# SW6124_A_A_B_C_Lighting_MCU_SEG.net
KiCad netlist of a schematic drawn in Altium Designer
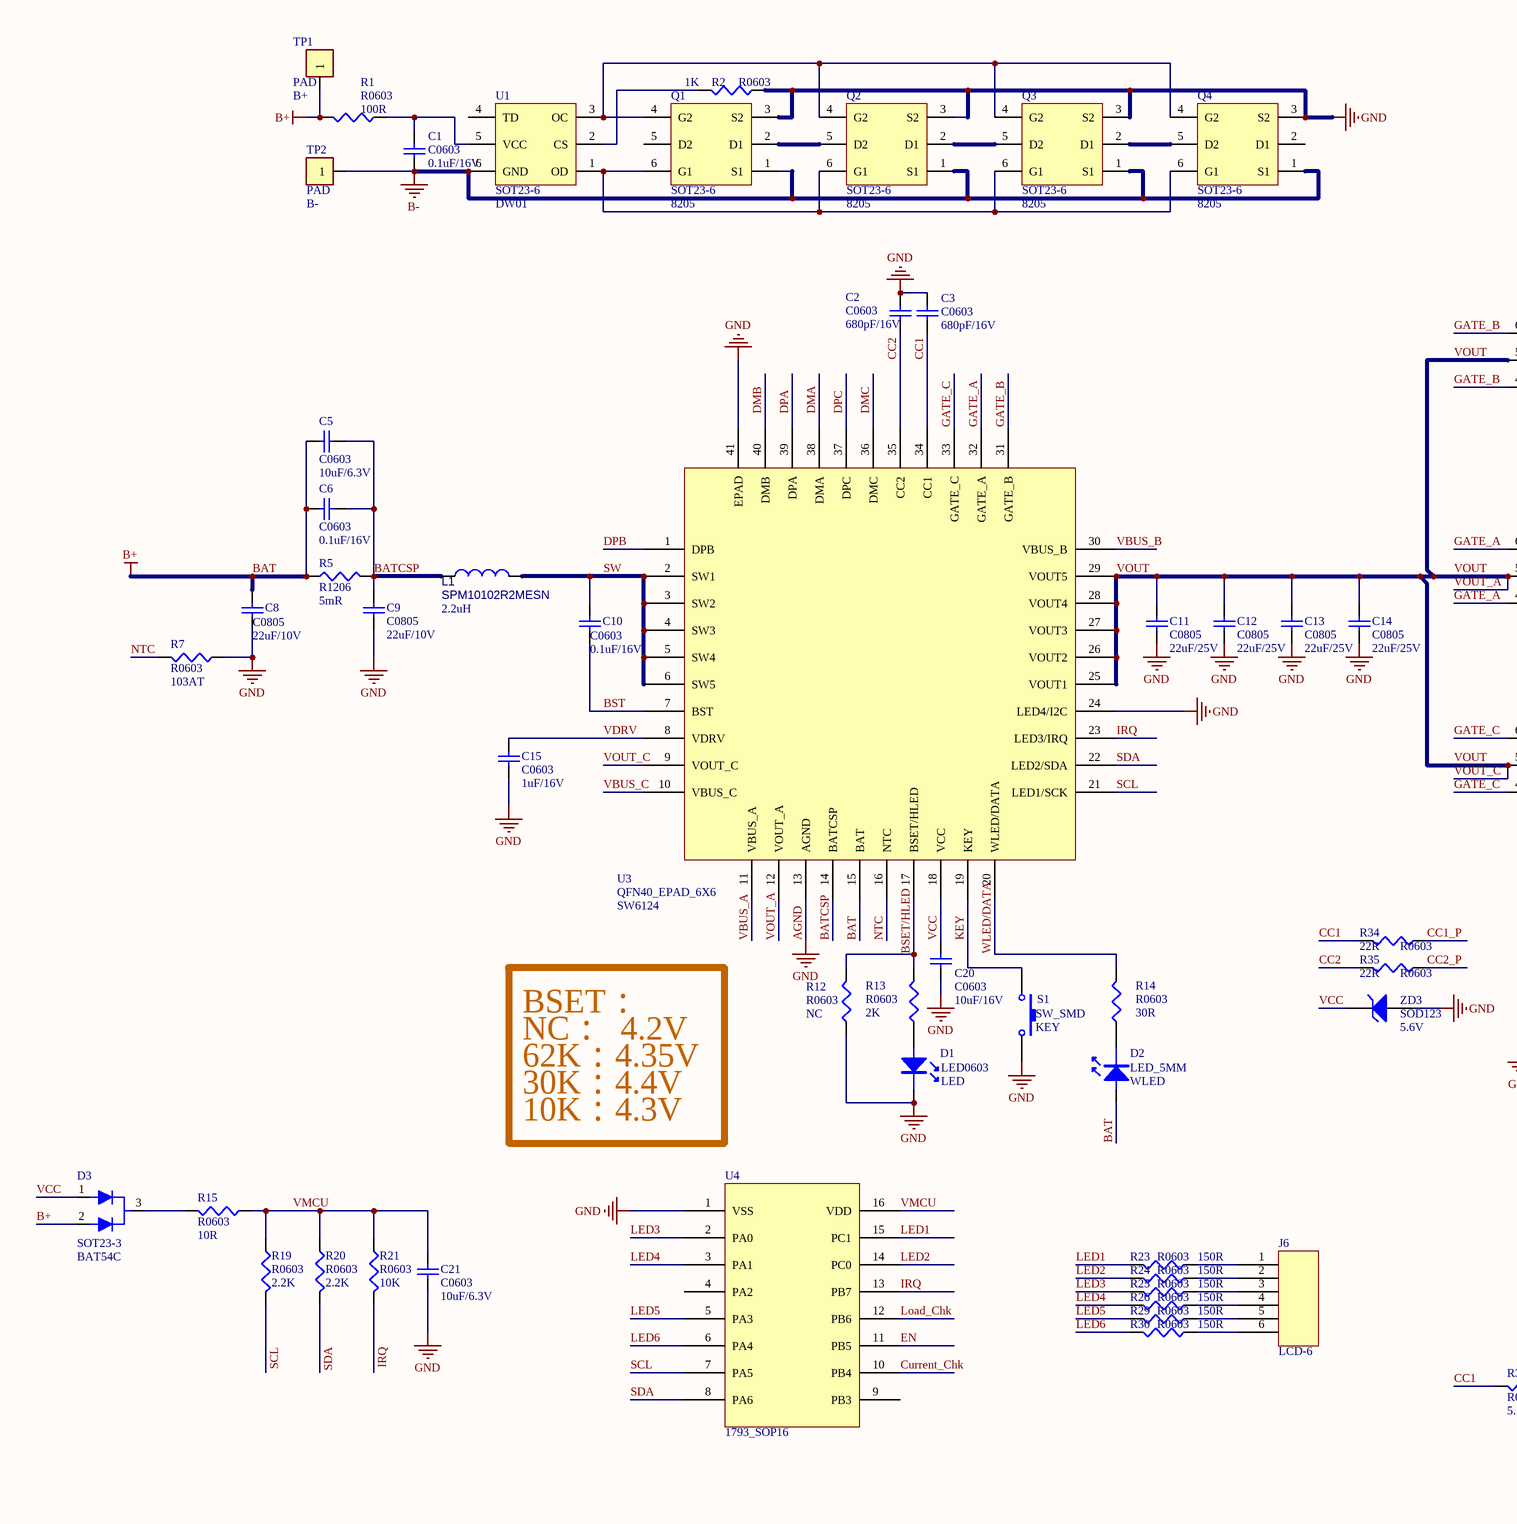
[diagram p0: SW6124+A+A+B+C+Lighting+MCU+SEG.SchDoc, left]
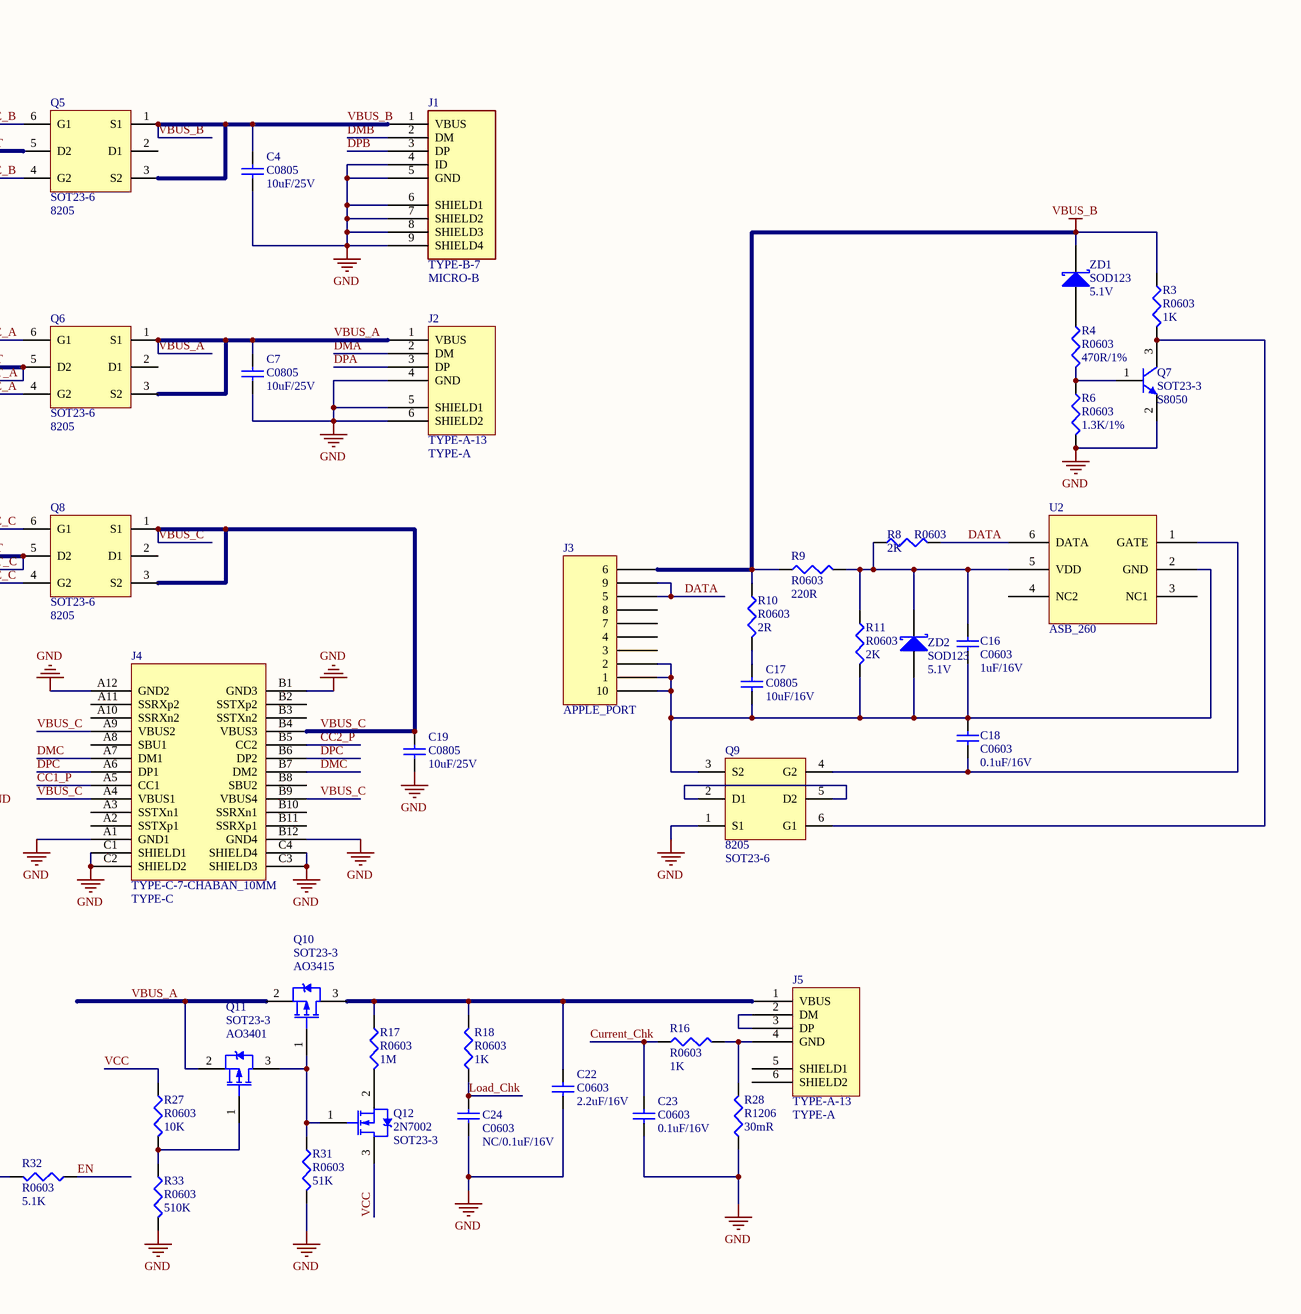
[diagram p1: SW6124+A+A+B+C+Lighting+MCU+SEG.SchDoc, right]

(export (version "E")
  (design (tool "Eeschema 10.0.6"))
  (components
    (comp (ref "C1")
      (value "C0603")
      (footprint "C0603")
      (description "Capacitor")
      (fields (field (name "ALTIUM_VALUE") "0.1uF/16V") (field (name "PUBLISHER") "Altium Limited"))
      (libsource (lib "*") (part "Cap"))
    )
    (comp (ref "C2")
      (value "C0603")
      (footprint "C0603")
      (description "Capacitor")
      (fields (field (name "ALTIUM_VALUE") "680pF/16V") (field (name "PUBLISHER") "Altium Limited"))
      (libsource (lib "*") (part "CAP0603"))
    )
    (comp (ref "C3")
      (value "C0603")
      (footprint "C0603")
      (description "Capacitor")
      (fields (field (name "ALTIUM_VALUE") "680pF/16V") (field (name "PUBLISHER") "Altium Limited"))
      (libsource (lib "*") (part "CAP0603"))
    )
    (comp (ref "C4")
      (value "C0805")
      (footprint "C0805")
      (description "Capacitor")
      (fields (field (name "ALTIUM_VALUE") "10uF/25V") (field (name "PUBLISHER") "Altium Limited"))
      (libsource (lib "*") (part "CAP0603"))
    )
    (comp (ref "C5")
      (value "C0603")
      (footprint "C0603")
      (description "Capacitor")
      (fields (field (name "ALTIUM_VALUE") "10uF/6.3V") (field (name "PUBLISHER") "Altium Limited"))
      (libsource (lib "*") (part "CAP0603"))
    )
    (comp (ref "C6")
      (value "C0603")
      (footprint "C0603")
      (description "Capacitor")
      (fields (field (name "ALTIUM_VALUE") "0.1uF/16V") (field (name "PUBLISHER") "Altium Limited"))
      (libsource (lib "*") (part "CAP0603"))
    )
    (comp (ref "C7")
      (value "C0805")
      (footprint "C0805")
      (description "Capacitor")
      (fields (field (name "ALTIUM_VALUE") "10uF/25V") (field (name "PUBLISHER") "Altium Limited"))
      (libsource (lib "*") (part "CAP0603"))
    )
    (comp (ref "C8")
      (value "C0805")
      (footprint "C0805")
      (description "Capacitor")
      (fields (field (name "ALTIUM_VALUE") "22uF/10V") (field (name "PUBLISHER") "Altium Limited"))
      (libsource (lib "*") (part "CAP0805"))
    )
    (comp (ref "C9")
      (value "C0805")
      (footprint "C0805")
      (description "Capacitor")
      (fields (field (name "ALTIUM_VALUE") "22uF/10V") (field (name "PUBLISHER") "Altium Limited"))
      (libsource (lib "*") (part "CAP0805"))
    )
    (comp (ref "C10")
      (value "C0603")
      (footprint "C0603")
      (description "Capacitor")
      (fields (field (name "ALTIUM_VALUE") "0.1uF/16V") (field (name "PUBLISHER") "Altium Limited"))
      (libsource (lib "*") (part "CAP0603"))
    )
    (comp (ref "C11")
      (value "C0805")
      (footprint "C0805")
      (description "Capacitor")
      (fields (field (name "ALTIUM_VALUE") "22uF/25V") (field (name "PUBLISHER") "Altium Limited"))
      (libsource (lib "*") (part "CAP0805"))
    )
    (comp (ref "C12")
      (value "C0805")
      (footprint "C0805")
      (description "Capacitor")
      (fields (field (name "ALTIUM_VALUE") "22uF/25V") (field (name "PUBLISHER") "Altium Limited"))
      (libsource (lib "*") (part "CAP0805"))
    )
    (comp (ref "C13")
      (value "C0805")
      (footprint "C0805")
      (description "Capacitor")
      (fields (field (name "ALTIUM_VALUE") "22uF/25V") (field (name "PUBLISHER") "Altium Limited"))
      (libsource (lib "*") (part "CAP0805"))
    )
    (comp (ref "C14")
      (value "C0805")
      (footprint "C0805")
      (description "Capacitor")
      (fields (field (name "ALTIUM_VALUE") "22uF/25V") (field (name "PUBLISHER") "Altium Limited"))
      (libsource (lib "*") (part "CAP0805"))
    )
    (comp (ref "C15")
      (value "C0603")
      (footprint "C0603")
      (description "Capacitor")
      (fields (field (name "ALTIUM_VALUE") "1uF/16V") (field (name "PUBLISHER") "Altium Limited"))
      (libsource (lib "*") (part "CAP0603"))
    )
    (comp (ref "C16")
      (value "C0603")
      (footprint "C0603")
      (description "Capacitor")
      (fields (field (name "ALTIUM_VALUE") "1uF/16V") (field (name "PUBLISHER") "Altium Limited"))
      (libsource (lib "*") (part "CAP0805"))
    )
    (comp (ref "C17")
      (value "C0805")
      (footprint "C0805")
      (description "Capacitor")
      (fields (field (name "ALTIUM_VALUE") "10uF/16V") (field (name "PUBLISHER") "Altium Limited"))
      (libsource (lib "*") (part "CAP0805"))
    )
    (comp (ref "C18")
      (value "C0603")
      (footprint "C0603")
      (description "Capacitor")
      (fields (field (name "ALTIUM_VALUE") "0.1uF/16V") (field (name "PUBLISHER") "Altium Limited"))
      (libsource (lib "*") (part "CAP0805"))
    )
    (comp (ref "C19")
      (value "C0805")
      (footprint "C0805")
      (description "Capacitor")
      (fields (field (name "ALTIUM_VALUE") "10uF/25V") (field (name "PUBLISHER") "Altium Limited"))
      (libsource (lib "*") (part "CAP0603"))
    )
    (comp (ref "C20")
      (value "C0603")
      (footprint "C0603")
      (description "Capacitor")
      (fields (field (name "ALTIUM_VALUE") "10uF/16V") (field (name "PUBLISHER") "Altium Limited"))
      (libsource (lib "*") (part "CAP0603"))
    )
    (comp (ref "C21")
      (value "C0603")
      (footprint "C0603")
      (description "Capacitor")
      (fields (field (name "ALTIUM_VALUE") "10uF/6.3V") (field (name "PUBLISHER") "Altium Limited"))
      (libsource (lib "*") (part "CAP0603"))
    )
    (comp (ref "C22")
      (value "C0603")
      (footprint "C0603")
      (description "Capacitor")
      (fields (field (name "ALTIUM_VALUE") "2.2uF/16V") (field (name "PUBLISHER") "Altium Limited"))
      (libsource (lib "*") (part "CAP0603"))
    )
    (comp (ref "C23")
      (value "C0603")
      (footprint "C0603")
      (description "Capacitor")
      (fields (field (name "ALTIUM_VALUE") "0.1uF/16V") (field (name "PUBLISHER") "Altium Limited"))
      (libsource (lib "*") (part "CAP0603"))
    )
    (comp (ref "C24")
      (value "C0603")
      (footprint "C0603")
      (description "Capacitor")
      (fields (field (name "ALTIUM_VALUE") "NC/0.1uF/16V") (field (name "PUBLISHER") "Altium Limited"))
      (libsource (lib "*") (part "CAP0603"))
    )
    (comp (ref "D1") (value "LED") (footprint "LED0603") (libsource (lib "*") (part "LED")))
    (comp (ref "D2")
      (value "WLED")
      (footprint "LED_5MM")
      (fields (field (name "FOOTPRINF") "LED_5MM") (field (name "Comment") "LED_5MM"))
      (libsource (lib "*") (part "LED"))
    )
    (comp (ref "D3") (value "BAT54C") (footprint "SOT23-3") (libsource (lib "Schlib1-2012") (part "D3")))
    (comp (ref "J1")
      (value "MICRO-B")
      (footprint "TYPE-B-7")
      (fields (field (name "FOOTPRINTF") "TYPE-B-7") (field (name "Comment") "USB_MICRO_B"))
      (libsource (lib "*") (part "USB_MICRO_B"))
    )
    (comp (ref "J2")
      (value "TYPE-A")
      (footprint "TYPE-A-13")
      (fields (field (name "FOOTPRINF") "TYPE-A-13") (field (name "Comment") "TYPE-A-1"))
      (libsource (lib "*") (part "TYPE-A-1"))
    )
    (comp (ref "J3") (value "APPLE_PORT") (libsource (lib "TEST") (part "APPLE_PORT")))
    (comp (ref "J4")
      (value "TYPE-C")
      (footprint "TYPE-C-7-CHABAN_10MM")
      (libsource (lib "*") (part "TYPE-C"))
    )
    (comp (ref "J5")
      (value "TYPE-A")
      (footprint "PIE10-USB")
      (fields (field (name "FOOTPRINF") "TYPE-A-13") (field (name "Comment") "TYPE-A-1"))
      (libsource (lib "*") (part "TYPE-A-1"))
    )
    (comp (ref "J6") (value "LCD-6") (libsource (lib "TEST") (part "LCD-6")))
    (comp (ref "L1")
      (value "SPM10102R2MESN")
      (footprint "INDUCTOR_SPM1010")
      (fields (field (name "ALTIUM_VALUE") "2.2uH"))
      (libsource (lib "*") (part "INDUCTOR"))
    )
    (comp (ref "Q1")
      (value "8205")
      (footprint "SOT23-6")
      (fields (field (name "FOOTPRINF") "SOT23-6"))
      (libsource (lib "") (part "8205B_2"))
    )
    (comp (ref "Q2")
      (value "8205")
      (footprint "SOT23-6")
      (fields (field (name "FOOTPRINF") "SOT23-6"))
      (libsource (lib "") (part "8205B_2"))
    )
    (comp (ref "Q3")
      (value "8205")
      (footprint "SOT23-6")
      (fields (field (name "FOOTPRINF") "SOT23-6"))
      (libsource (lib "") (part "8205B_2"))
    )
    (comp (ref "Q4")
      (value "8205")
      (footprint "SOT23-6")
      (fields (field (name "FOOTPRINF") "SOT23-6"))
      (libsource (lib "") (part "8205B_2"))
    )
    (comp (ref "Q5")
      (value "8205")
      (footprint "SOT23-6")
      (fields (field (name "FOOTPRINF") "SOT23-6"))
      (libsource (lib "") (part "8205B_1"))
    )
    (comp (ref "Q6")
      (value "8205")
      (footprint "SOT23-6")
      (fields (field (name "FOOTPRINF") "SOT23-6"))
      (libsource (lib "") (part "8205B_1"))
    )
    (comp (ref "Q7")
      (value "S8050")
      (footprint "SOT23-3")
      (description "NPN General Purpose Amplifier")
      (fields (field (name "PUBLISHER") "Altium Limited"))
      (libsource (lib "Miscellaneous Devices") (part "2N3904"))
    )
    (comp (ref "Q8")
      (value "8205")
      (footprint "SOT23-6")
      (fields (field (name "FOOTPRINF") "SOT23-6"))
      (libsource (lib "") (part "8205B_1"))
    )
    (comp (ref "Q9")
      (value "8205")
      (footprint "SOT23-6")
      (fields (field (name "FOOTPRINF") "SOT23-6"))
      (libsource (lib "*") (part "8205B"))
    )
    (comp (ref "Q10")
      (value "AO3415")
      (footprint "SOT23-3")
      (description "P-Channel Power MOSFET")
      (fields (field (name "Comment") "PMOS-2") (field (name "PUBLISHER") "Altium Limited"))
      (libsource (lib "Miscellaneous Devices") (part "PMOS-2"))
    )
    (comp (ref "Q11")
      (value "AO3401")
      (footprint "SOT23-3")
      (description "P-Channel Power MOSFET")
      (fields (field (name "Comment") "PMOS-2") (field (name "PUBLISHER") "Altium Limited"))
      (libsource (lib "Miscellaneous Devices") (part "PMOS-2"))
    )
    (comp (ref "Q12")
      (value "2N7002")
      (footprint "SOT23-3")
      (description "N-Channel Power MOSFET")
      (fields (field (name "Comment") "NMOS-2") (field (name "PUBLISHER") "Altium Limited"))
      (libsource (lib "Miscellaneous Devices") (part "NMOS-2"))
    )
    (comp (ref "R1")
      (value "R0603")
      (footprint "R0603")
      (description "Resistor")
      (fields (field (name "ALTIUM_VALUE") "100R") (field (name "PUBLISHER") "Altium Limited"))
      (libsource (lib "*") (part "Res3"))
    )
    (comp (ref "R2")
      (value "R0603")
      (footprint "R0603")
      (description "Resistor")
      (fields (field (name "ALTIUM_VALUE") "1K") (field (name "PUBLISHER") "Altium Limited"))
      (libsource (lib "*") (part "Res3"))
    )
    (comp (ref "R3")
      (value "R0603")
      (footprint "R0603")
      (description "Resistor")
      (fields (field (name "ALTIUM_VALUE") "1K") (field (name "PUBLISHER") "Altium Limited"))
      (libsource (lib "Miscellaneous Devices") (part "Res3"))
    )
    (comp (ref "R4")
      (value "R0603")
      (footprint "R0603")
      (description "Resistor")
      (fields (field (name "ALTIUM_VALUE") "470R/1%") (field (name "PUBLISHER") "Altium Limited"))
      (libsource (lib "Miscellaneous Devices") (part "Res3"))
    )
    (comp (ref "R5")
      (value "R1206")
      (footprint "R1206")
      (description "Resistor")
      (fields (field (name "ALTIUM_VALUE") "5mR") (field (name "PUBLISHER") "Altium Limited"))
      (libsource (lib "*") (part "RES"))
    )
    (comp (ref "R6")
      (value "R0603")
      (footprint "R0603")
      (description "Resistor")
      (fields (field (name "ALTIUM_VALUE") "1.3K/1%") (field (name "PUBLISHER") "Altium Limited"))
      (libsource (lib "Miscellaneous Devices") (part "Res3"))
    )
    (comp (ref "R7")
      (value "R0603")
      (footprint "R0603")
      (description "Resistor")
      (fields (field (name "ALTIUM_VALUE") "103AT") (field (name "PUBLISHER") "Altium Limited"))
      (libsource (lib "*") (part "RES"))
    )
    (comp (ref "R8")
      (value "R0603")
      (footprint "R0603")
      (description "Resistor")
      (fields (field (name "ALTIUM_VALUE") "2K") (field (name "PUBLISHER") "Altium Limited"))
      (libsource (lib "Miscellaneous Devices") (part "Res3"))
    )
    (comp (ref "R9")
      (value "R0603")
      (footprint "R0603")
      (description "Resistor")
      (fields (field (name "ALTIUM_VALUE") "220R") (field (name "PUBLISHER") "Altium Limited"))
      (libsource (lib "Miscellaneous Devices") (part "Res3"))
    )
    (comp (ref "R10")
      (value "R0603")
      (footprint "R0603")
      (description "Resistor")
      (fields (field (name "ALTIUM_VALUE") "2R") (field (name "PUBLISHER") "Altium Limited"))
      (libsource (lib "Miscellaneous Devices") (part "Res3"))
    )
    (comp (ref "R11")
      (value "R0603")
      (footprint "R0603")
      (description "Resistor")
      (fields (field (name "ALTIUM_VALUE") "2K") (field (name "PUBLISHER") "Altium Limited"))
      (libsource (lib "Miscellaneous Devices") (part "Res3"))
    )
    (comp (ref "R12")
      (value "R0603")
      (footprint "R0603")
      (description "Resistor")
      (fields (field (name "ALTIUM_VALUE") "NC") (field (name "PUBLISHER") "Altium Limited"))
      (libsource (lib "*") (part "RES"))
    )
    (comp (ref "R13")
      (value "R0603")
      (footprint "R0603")
      (description "Resistor")
      (fields (field (name "ALTIUM_VALUE") "2K") (field (name "PUBLISHER") "Altium Limited"))
      (libsource (lib "*") (part "RES"))
    )
    (comp (ref "R14")
      (value "R0603")
      (footprint "R0603")
      (description "Resistor")
      (fields (field (name "ALTIUM_VALUE") "30R") (field (name "PUBLISHER") "Altium Limited"))
      (libsource (lib "*") (part "RES"))
    )
    (comp (ref "R15")
      (value "R0603")
      (footprint "R0603")
      (description "Resistor")
      (fields (field (name "ALTIUM_VALUE") "10R") (field (name "PUBLISHER") "Altium Limited"))
      (libsource (lib "*") (part "RES"))
    )
    (comp (ref "R16")
      (value "R0603")
      (footprint "R0603")
      (description "Resistor")
      (fields (field (name "ALTIUM_VALUE") "1K") (field (name "PUBLISHER") "Altium Limited"))
      (libsource (lib "*") (part "RES"))
    )
    (comp (ref "R17")
      (value "R0603")
      (footprint "R0603")
      (description "Resistor")
      (fields (field (name "ALTIUM_VALUE") "1M") (field (name "PUBLISHER") "Altium Limited"))
      (libsource (lib "*") (part "RES"))
    )
    (comp (ref "R18")
      (value "R0603")
      (footprint "R0603")
      (description "Resistor")
      (fields (field (name "ALTIUM_VALUE") "1K") (field (name "PUBLISHER") "Altium Limited"))
      (libsource (lib "*") (part "RES"))
    )
    (comp (ref "R19")
      (value "R0603")
      (footprint "R0603")
      (description "Resistor")
      (fields (field (name "ALTIUM_VALUE") "2.2K") (field (name "PUBLISHER") "Altium Limited"))
      (libsource (lib "*") (part "RES"))
    )
    (comp (ref "R20")
      (value "R0603")
      (footprint "R0603")
      (description "Resistor")
      (fields (field (name "ALTIUM_VALUE") "2.2K") (field (name "PUBLISHER") "Altium Limited"))
      (libsource (lib "*") (part "RES"))
    )
    (comp (ref "R21")
      (value "R0603")
      (footprint "R0603")
      (description "Resistor")
      (fields (field (name "ALTIUM_VALUE") "10K") (field (name "PUBLISHER") "Altium Limited"))
      (libsource (lib "*") (part "RES"))
    )
    (comp (ref "R23")
      (value "R0603")
      (footprint "R0603")
      (description "Resistor")
      (fields (field (name "ALTIUM_VALUE") "150R") (field (name "PUBLISHER") "Altium Limited"))
      (libsource (lib "*") (part "RES"))
    )
    (comp (ref "R24")
      (value "R0603")
      (footprint "R0603")
      (description "Resistor")
      (fields (field (name "ALTIUM_VALUE") "150R") (field (name "PUBLISHER") "Altium Limited"))
      (libsource (lib "*") (part "RES"))
    )
    (comp (ref "R25")
      (value "R0603")
      (footprint "R0603")
      (description "Resistor")
      (fields (field (name "ALTIUM_VALUE") "150R") (field (name "PUBLISHER") "Altium Limited"))
      (libsource (lib "*") (part "RES"))
    )
    (comp (ref "R26")
      (value "R0603")
      (footprint "R0603")
      (description "Resistor")
      (fields (field (name "ALTIUM_VALUE") "150R") (field (name "PUBLISHER") "Altium Limited"))
      (libsource (lib "*") (part "RES"))
    )
    (comp (ref "R27")
      (value "R0603")
      (footprint "R0603")
      (description "Resistor")
      (fields (field (name "ALTIUM_VALUE") "10K") (field (name "PUBLISHER") "Altium Limited"))
      (libsource (lib "*") (part "RES"))
    )
    (comp (ref "R28")
      (value "R1206")
      (footprint "C-1206A")
      (description "Resistor")
      (fields (field (name "ALTIUM_VALUE") "30mR") (field (name "PUBLISHER") "Altium Limited"))
      (libsource (lib "*") (part "RES"))
    )
    (comp (ref "R29")
      (value "R0603")
      (footprint "R0603")
      (description "Resistor")
      (fields (field (name "ALTIUM_VALUE") "150R") (field (name "PUBLISHER") "Altium Limited"))
      (libsource (lib "*") (part "RES"))
    )
    (comp (ref "R30")
      (value "R0603")
      (footprint "R0603")
      (description "Resistor")
      (fields (field (name "ALTIUM_VALUE") "150R") (field (name "PUBLISHER") "Altium Limited"))
      (libsource (lib "*") (part "RES"))
    )
    (comp (ref "R31")
      (value "R0603")
      (footprint "R0603")
      (description "Resistor")
      (fields (field (name "ALTIUM_VALUE") "51K") (field (name "PUBLISHER") "Altium Limited"))
      (libsource (lib "*") (part "RES"))
    )
    (comp (ref "R32")
      (value "R0603")
      (footprint "R0603")
      (description "Resistor")
      (fields (field (name "ALTIUM_VALUE") "5.1K") (field (name "PUBLISHER") "Altium Limited"))
      (libsource (lib "*") (part "RES"))
    )
    (comp (ref "R33")
      (value "R0603")
      (footprint "R0603")
      (description "Resistor")
      (fields (field (name "ALTIUM_VALUE") "510K") (field (name "PUBLISHER") "Altium Limited"))
      (libsource (lib "*") (part "RES"))
    )
    (comp (ref "R34")
      (value "R0603")
      (footprint "R0603")
      (description "Resistor")
      (fields (field (name "ALTIUM_VALUE") "22R") (field (name "PUBLISHER") "Altium Limited"))
      (libsource (lib "*") (part "RES"))
    )
    (comp (ref "R35")
      (value "R0603")
      (footprint "R0603")
      (description "Resistor")
      (fields (field (name "ALTIUM_VALUE") "22R") (field (name "PUBLISHER") "Altium Limited"))
      (libsource (lib "*") (part "RES"))
    )
    (comp (ref "S1")
      (value "KEY")
      (footprint "SW_SMD")
      (fields (field (name "FOOTPRINF") "SW_SMD"))
      (libsource (lib "*") (part "SW K"))
    )
    (comp (ref "TP1") (value "B+") (footprint "PAD") (libsource (lib "") (part "Test Point_1")))
    (comp (ref "TP2") (value "B-") (footprint "PAD") (libsource (lib "*") (part "Test Point")))
    (comp (ref "U1")
      (value "DW01")
      (footprint "SOT23-6")
      (fields (field (name "FOOTPRINF") "SOT23-6"))
      (libsource (lib "*") (part "DW01"))
    )
    (comp (ref "U2") (value "ASB_260") (footprint "SOT-23-") (libsource (lib "TEST") (part "ASB_260")))
    (comp (ref "U3")
      (value "SW6124")
      (footprint "QFN40_EPAD_6X6")
      (libsource (lib "TEST") (part "SW6106_AFC"))
    )
    (comp (ref "U4") (value "1793_SOP16") (libsource (lib "TEST") (part "1793_SOP16")))
    (comp (ref "ZD1")
      (value "5.1V")
      (footprint "SOD123")
      (description "Schottky Rectifier")
      (fields (field (name "Comment") "Diode 11DQ03") (field (name "PUBLISHER") "Altium Limited"))
      (libsource (lib "Miscellaneous Devices") (part "Diode 11DQ03"))
    )
    (comp (ref "ZD2")
      (value "5.1V")
      (footprint "SOD123")
      (description "Schottky Rectifier")
      (fields (field (name "Comment") "Diode 11DQ03") (field (name "PUBLISHER") "Altium Limited"))
      (libsource (lib "Miscellaneous Devices") (part "Diode 11DQ03"))
    )
    (comp (ref "ZD3")
      (value "SOD123")
      (footprint "SOD-123")
      (description "Zener Diode")
      (fields (field (name "ALTIUM_UNNAMED_1") "5.6V"))
      (libsource (lib "Miscellaneous Devices") (part "D Zener"))
    )
  )
  (nets
    (net (code "1") (name "/BATCSP") (class "Default")
      (node (ref "C5") (pin "2") (pinfunction "2_2") (pintype "passive"))
      (node (ref "C6") (pin "2") (pinfunction "2_2") (pintype "passive"))
      (node (ref "C9") (pin "2") (pinfunction "2_2") (pintype "passive"))
      (node (ref "L1") (pin "1") (pinfunction "1_1") (pintype "passive"))
      (node (ref "R5") (pin "2") (pinfunction "2_2") (pintype "passive"))
      (node (ref "U3") (pin "14") (pinfunction "BATCSP_14") (pintype "passive"))
    )
    (net (code "2") (name "/BSET{slash}HLED") (class "Default")
      (node (ref "R12") (pin "2") (pinfunction "2_2") (pintype "passive"))
      (node (ref "R13") (pin "2") (pinfunction "2_2") (pintype "passive"))
      (node (ref "U3") (pin "17") (pinfunction "BSET/HLED_17") (pintype "passive"))
    )
    (net (code "3") (name "/BST") (class "Default")
      (node (ref "C10") (pin "1") (pinfunction "1_1") (pintype "passive"))
      (node (ref "U3") (pin "7") (pinfunction "BST_7") (pintype "passive"))
    )
    (net (code "4") (name "/CC1") (class "Default")
      (node (ref "C3") (pin "1") (pinfunction "1_1") (pintype "passive"))
      (node (ref "R32") (pin "2") (pinfunction "2_2") (pintype "passive"))
      (node (ref "R34") (pin "2") (pinfunction "2_2") (pintype "passive"))
      (node (ref "U3") (pin "34") (pinfunction "CC1_34") (pintype "passive"))
    )
    (net (code "5") (name "/CC1_P") (class "Default")
      (node (ref "J4") (pin "A5") (pinfunction "CC1_A5") (pintype "passive"))
      (node (ref "R34") (pin "1") (pinfunction "1_1") (pintype "passive"))
    )
    (net (code "6") (name "/CC2") (class "Default")
      (node (ref "C2") (pin "1") (pinfunction "1_1") (pintype "passive"))
      (node (ref "R35") (pin "2") (pinfunction "2_2") (pintype "passive"))
      (node (ref "U3") (pin "35") (pinfunction "CC2_35") (pintype "passive"))
    )
    (net (code "7") (name "/CC2_P") (class "Default")
      (node (ref "J4") (pin "B5") (pinfunction "CC2_B5") (pintype "passive"))
      (node (ref "R35") (pin "1") (pinfunction "1_1") (pintype "passive"))
    )
    (net (code "8") (name "/Current_Chk") (class "Default")
      (node (ref "C23") (pin "2") (pinfunction "2_2") (pintype "passive"))
      (node (ref "R16") (pin "1") (pinfunction "1_1") (pintype "passive"))
      (node (ref "U4") (pin "10") (pinfunction "PB4_10") (pintype "passive"))
    )
    (net (code "9") (name "/DATA") (class "Default")
      (node (ref "J3") (pin "5") (pinfunction "5_5") (pintype "passive"))
      (node (ref "J3") (pin "9") (pinfunction "9_9") (pintype "passive"))
      (node (ref "R8") (pin "2") (pinfunction "2_2") (pintype "passive"))
      (node (ref "U2") (pin "6") (pinfunction "DATA_6") (pintype "passive"))
    )
    (net (code "10") (name "/DMA") (class "Default")
      (node (ref "J2") (pin "2") (pinfunction "DM_2") (pintype "passive"))
      (node (ref "U3") (pin "38") (pinfunction "DMA_38") (pintype "passive"))
    )
    (net (code "11") (name "/DMB") (class "Default")
      (node (ref "J1") (pin "2") (pinfunction "DM_2") (pintype "passive"))
      (node (ref "U3") (pin "40") (pinfunction "DMB_40") (pintype "passive"))
    )
    (net (code "12") (name "/DMC") (class "Default")
      (node (ref "J4") (pin "A7") (pinfunction "DM1_A7") (pintype "passive"))
      (node (ref "J4") (pin "B7") (pinfunction "DM2_B7") (pintype "passive"))
      (node (ref "U3") (pin "36") (pinfunction "DMC_36") (pintype "passive"))
    )
    (net (code "13") (name "/DPA") (class "Default")
      (node (ref "J2") (pin "3") (pinfunction "DP_3") (pintype "passive"))
      (node (ref "U3") (pin "39") (pinfunction "DPA_39") (pintype "passive"))
    )
    (net (code "14") (name "/DPB") (class "Default")
      (node (ref "J1") (pin "3") (pinfunction "DP_3") (pintype "passive"))
      (node (ref "U3") (pin "1") (pinfunction "DPB_1") (pintype "passive"))
    )
    (net (code "15") (name "/DPC") (class "Default")
      (node (ref "J4") (pin "A6") (pinfunction "DP1_A6") (pintype "passive"))
      (node (ref "J4") (pin "B6") (pinfunction "DP2_B6") (pintype "passive"))
      (node (ref "U3") (pin "37") (pinfunction "DPC_37") (pintype "passive"))
    )
    (net (code "16") (name "/EN") (class "Default")
      (node (ref "R32") (pin "1") (pinfunction "1_1") (pintype "passive"))
      (node (ref "U4") (pin "11") (pinfunction "PB5_11") (pintype "passive"))
    )
    (net (code "17") (name "/GATE_A") (class "Default")
      (node (ref "Q6") (pin "4") (pinfunction "G2_4") (pintype "passive"))
      (node (ref "Q6") (pin "6") (pinfunction "G1_6") (pintype "passive"))
      (node (ref "U3") (pin "32") (pinfunction "GATE_A_32") (pintype "passive"))
    )
    (net (code "18") (name "/GATE_B") (class "Default")
      (node (ref "Q5") (pin "4") (pinfunction "G2_4") (pintype "passive"))
      (node (ref "Q5") (pin "6") (pinfunction "G1_6") (pintype "passive"))
      (node (ref "U3") (pin "31") (pinfunction "GATE_B_31") (pintype "passive"))
    )
    (net (code "19") (name "/GATE_C") (class "Default")
      (node (ref "Q8") (pin "4") (pinfunction "G2_4") (pintype "passive"))
      (node (ref "Q8") (pin "6") (pinfunction "G1_6") (pintype "passive"))
      (node (ref "U3") (pin "33") (pinfunction "GATE_C_33") (pintype "passive"))
    )
    (net (code "20") (name "/IRQ") (class "Default")
      (node (ref "R21") (pin "2") (pinfunction "2_2") (pintype "passive"))
      (node (ref "U3") (pin "23") (pinfunction "LED3/IRQ_23") (pintype "passive"))
      (node (ref "U4") (pin "13") (pinfunction "PB7_13") (pintype "passive"))
    )
    (net (code "21") (name "/KEY") (class "Default")
      (node (ref "S1") (pin "1") (pinfunction "1_1") (pintype "passive"))
      (node (ref "U3") (pin "19") (pinfunction "KEY_19") (pintype "passive"))
    )
    (net (code "22") (name "/LED1") (class "Default")
      (node (ref "R23") (pin "2") (pinfunction "2_2") (pintype "passive"))
      (node (ref "U4") (pin "15") (pinfunction "PC1_15") (pintype "passive"))
    )
    (net (code "23") (name "/LED2") (class "Default")
      (node (ref "R24") (pin "2") (pinfunction "2_2") (pintype "passive"))
      (node (ref "U4") (pin "14") (pinfunction "PC0_14") (pintype "passive"))
    )
    (net (code "24") (name "/LED3") (class "Default")
      (node (ref "R25") (pin "2") (pinfunction "2_2") (pintype "passive"))
      (node (ref "U4") (pin "2") (pinfunction "PA0_2") (pintype "passive"))
    )
    (net (code "25") (name "/LED4") (class "Default")
      (node (ref "R26") (pin "2") (pinfunction "2_2") (pintype "passive"))
      (node (ref "U4") (pin "3") (pinfunction "PA1_3") (pintype "passive"))
    )
    (net (code "26") (name "/LED5") (class "Default")
      (node (ref "R29") (pin "2") (pinfunction "2_2") (pintype "passive"))
      (node (ref "U4") (pin "5") (pinfunction "PA3_5") (pintype "passive"))
    )
    (net (code "27") (name "/LED6") (class "Default")
      (node (ref "R30") (pin "2") (pinfunction "2_2") (pintype "passive"))
      (node (ref "U4") (pin "6") (pinfunction "PA4_6") (pintype "passive"))
    )
    (net (code "28") (name "/Load_Chk") (class "Default")
      (node (ref "C24") (pin "2") (pinfunction "2_2") (pintype "passive"))
      (node (ref "R18") (pin "1") (pinfunction "1_1") (pintype "passive"))
      (node (ref "U4") (pin "12") (pinfunction "PB6_12") (pintype "passive"))
    )
    (net (code "29") (name "/NTC") (class "Default")
      (node (ref "R7") (pin "2") (pinfunction "2_2") (pintype "passive"))
      (node (ref "U3") (pin "16") (pinfunction "NTC_16") (pintype "passive"))
    )
    (net (code "30") (name "/SCL") (class "Default")
      (node (ref "R19") (pin "2") (pinfunction "2_2") (pintype "passive"))
      (node (ref "U3") (pin "21") (pinfunction "LED1/SCK_21") (pintype "passive"))
      (node (ref "U4") (pin "7") (pinfunction "PA5_7") (pintype "passive"))
    )
    (net (code "31") (name "/SDA") (class "Default")
      (node (ref "R20") (pin "2") (pinfunction "2_2") (pintype "passive"))
      (node (ref "U3") (pin "22") (pinfunction "LED2/SDA_22") (pintype "passive"))
      (node (ref "U4") (pin "8") (pinfunction "PA6_8") (pintype "passive"))
    )
    (net (code "32") (name "/SW") (class "Default")
      (node (ref "C10") (pin "2") (pinfunction "2_2") (pintype "passive"))
      (node (ref "L1") (pin "2") (pinfunction "2_2") (pintype "passive"))
      (node (ref "U3") (pin "2") (pinfunction "SW1_2") (pintype "passive"))
      (node (ref "U3") (pin "3") (pinfunction "SW2_3") (pintype "passive"))
      (node (ref "U3") (pin "4") (pinfunction "SW3_4") (pintype "passive"))
      (node (ref "U3") (pin "5") (pinfunction "SW4_5") (pintype "passive"))
      (node (ref "U3") (pin "6") (pinfunction "SW5_6") (pintype "passive"))
    )
    (net (code "33") (name "/VBUS_A") (class "Default")
      (node (ref "C7") (pin "2") (pinfunction "2_2") (pintype "passive"))
      (node (ref "J2") (pin "1") (pinfunction "VBUS_1") (pintype "passive"))
      (node (ref "Q10") (pin "2") (pinfunction "S_2") (pintype "passive"))
      (node (ref "Q11") (pin "2") (pinfunction "S_2") (pintype "passive"))
      (node (ref "Q6") (pin "1") (pinfunction "S1_1") (pintype "passive"))
      (node (ref "Q6") (pin "3") (pinfunction "S2_3") (pintype "passive"))
      (node (ref "U3") (pin "11") (pinfunction "VBUS_A_11") (pintype "passive"))
    )
    (net (code "34") (name "/VBUS_C") (class "Default")
      (node (ref "C19") (pin "2") (pinfunction "2_2") (pintype "passive"))
      (node (ref "J4") (pin "A4") (pinfunction "VBUS1_A4") (pintype "passive"))
      (node (ref "J4") (pin "A9") (pinfunction "VBUS2_A9") (pintype "passive"))
      (node (ref "J4") (pin "B4") (pinfunction "VBUS3_B4") (pintype "passive"))
      (node (ref "J4") (pin "B9") (pinfunction "VBUS4_B9") (pintype "passive"))
      (node (ref "Q8") (pin "1") (pinfunction "S1_1") (pintype "passive"))
      (node (ref "Q8") (pin "3") (pinfunction "S2_3") (pintype "passive"))
      (node (ref "U3") (pin "10") (pinfunction "VBUS_C_10") (pintype "passive"))
    )
    (net (code "35") (name "/VCC") (class "Default")
      (node (ref "C20") (pin "2") (pinfunction "2_2") (pintype "passive"))
      (node (ref "D3") (pin "1") (pintype "passive"))
      (node (ref "Q12") (pin "3") (pinfunction "D_3") (pintype "passive"))
      (node (ref "R27") (pin "1") (pinfunction "1_1") (pintype "passive"))
      (node (ref "U3") (pin "18") (pinfunction "VCC_18") (pintype "passive"))
      (node (ref "ZD3") (pin "2") (pinfunction "K_2") (pintype "passive"))
    )
    (net (code "36") (name "/VDRV") (class "Default")
      (node (ref "C15") (pin "2") (pinfunction "2_2") (pintype "passive"))
      (node (ref "U3") (pin "8") (pinfunction "VDRV_8") (pintype "passive"))
    )
    (net (code "37") (name "/VMCU") (class "Default")
      (node (ref "C21") (pin "1") (pinfunction "1_1") (pintype "passive"))
      (node (ref "R15") (pin "1") (pinfunction "1_1") (pintype "passive"))
      (node (ref "R19") (pin "1") (pinfunction "1_1") (pintype "passive"))
      (node (ref "R20") (pin "1") (pinfunction "1_1") (pintype "passive"))
      (node (ref "R21") (pin "1") (pinfunction "1_1") (pintype "passive"))
      (node (ref "U4") (pin "16") (pinfunction "VDD_16") (pintype "passive"))
    )
    (net (code "38") (name "/VOUT") (class "Default")
      (node (ref "C11") (pin "2") (pinfunction "2_2") (pintype "passive"))
      (node (ref "C12") (pin "2") (pinfunction "2_2") (pintype "passive"))
      (node (ref "C13") (pin "2") (pinfunction "2_2") (pintype "passive"))
      (node (ref "C14") (pin "2") (pinfunction "2_2") (pintype "passive"))
      (node (ref "Q5") (pin "5") (pinfunction "D2_5") (pintype "passive"))
      (node (ref "Q6") (pin "5") (pinfunction "D2_5") (pintype "passive"))
      (node (ref "Q8") (pin "5") (pinfunction "D2_5") (pintype "passive"))
      (node (ref "U3") (pin "12") (pinfunction "VOUT_A_12") (pintype "passive"))
      (node (ref "U3") (pin "25") (pinfunction "VOUT1_25") (pintype "passive"))
      (node (ref "U3") (pin "26") (pinfunction "VOUT2_26") (pintype "passive"))
      (node (ref "U3") (pin "27") (pinfunction "VOUT3_27") (pintype "passive"))
      (node (ref "U3") (pin "28") (pinfunction "VOUT4_28") (pintype "passive"))
      (node (ref "U3") (pin "29") (pinfunction "VOUT5_29") (pintype "passive"))
      (node (ref "U3") (pin "9") (pinfunction "VOUT_C_9") (pintype "passive"))
    )
    (net (code "39") (name "/WLED{slash}DATA") (class "Default")
      (node (ref "R14") (pin "2") (pinfunction "2_2") (pintype "passive"))
      (node (ref "U3") (pin "20") (pinfunction "WLED/DATA_20") (pintype "passive"))
    )
    (net (code "40") (name "B+") (class "Default")
      (node (ref "C5") (pin "1") (pinfunction "1_1") (pintype "passive"))
      (node (ref "C6") (pin "1") (pinfunction "1_1") (pintype "passive"))
      (node (ref "C8") (pin "2") (pinfunction "2_2") (pintype "passive"))
      (node (ref "D2") (pin "1") (pinfunction "A_1") (pintype "passive"))
      (node (ref "D3") (pin "2") (pintype "passive"))
      (node (ref "R1") (pin "2") (pinfunction "2_2") (pintype "passive"))
      (node (ref "R5") (pin "1") (pinfunction "1_1") (pintype "passive"))
      (node (ref "TP1") (pin "1") (pinfunction "1_1") (pintype "passive"))
      (node (ref "U3") (pin "15") (pinfunction "BAT_15") (pintype "passive"))
    )
    (net (code "41") (name "B-") (class "Default")
      (node (ref "C1") (pin "1") (pinfunction "1_1") (pintype "passive"))
      (node (ref "Q1") (pin "1") (pinfunction "S1_1") (pintype "passive"))
      (node (ref "Q2") (pin "1") (pinfunction "S1_1") (pintype "passive"))
      (node (ref "Q3") (pin "1") (pinfunction "S1_1") (pintype "passive"))
      (node (ref "Q4") (pin "1") (pinfunction "S1_1") (pintype "passive"))
      (node (ref "TP2") (pin "1") (pinfunction "1_1") (pintype "passive"))
      (node (ref "U1") (pin "6") (pinfunction "GND_6") (pintype "passive"))
    )
    (net (code "42") (name "GND") (class "Default")
      (node (ref "C11") (pin "1") (pinfunction "1_1") (pintype "passive"))
      (node (ref "C12") (pin "1") (pinfunction "1_1") (pintype "passive"))
      (node (ref "C13") (pin "1") (pinfunction "1_1") (pintype "passive"))
      (node (ref "C14") (pin "1") (pinfunction "1_1") (pintype "passive"))
      (node (ref "C15") (pin "1") (pinfunction "1_1") (pintype "passive"))
      (node (ref "C19") (pin "1") (pinfunction "1_1") (pintype "passive"))
      (node (ref "C2") (pin "2") (pinfunction "2_2") (pintype "passive"))
      (node (ref "C20") (pin "1") (pinfunction "1_1") (pintype "passive"))
      (node (ref "C21") (pin "2") (pinfunction "2_2") (pintype "passive"))
      (node (ref "C22") (pin "1") (pinfunction "1_1") (pintype "passive"))
      (node (ref "C23") (pin "1") (pinfunction "1_1") (pintype "passive"))
      (node (ref "C24") (pin "1") (pinfunction "1_1") (pintype "passive"))
      (node (ref "C3") (pin "2") (pinfunction "2_2") (pintype "passive"))
      (node (ref "C4") (pin "1") (pinfunction "1_1") (pintype "passive"))
      (node (ref "C7") (pin "1") (pinfunction "1_1") (pintype "passive"))
      (node (ref "C8") (pin "1") (pinfunction "1_1") (pintype "passive"))
      (node (ref "C9") (pin "1") (pinfunction "1_1") (pintype "passive"))
      (node (ref "D1") (pin "2") (pinfunction "K_2") (pintype "passive"))
      (node (ref "J1") (pin "4") (pinfunction "ID_4") (pintype "passive"))
      (node (ref "J1") (pin "5") (pinfunction "GND_5") (pintype "passive"))
      (node (ref "J1") (pin "6") (pinfunction "SHIELD1_6") (pintype "passive"))
      (node (ref "J1") (pin "7") (pinfunction "SHIELD2_7") (pintype "passive"))
      (node (ref "J1") (pin "8") (pinfunction "SHIELD3_8") (pintype "passive"))
      (node (ref "J1") (pin "9") (pinfunction "SHIELD4_9") (pintype "passive"))
      (node (ref "J2") (pin "4") (pinfunction "GND_4") (pintype "passive"))
      (node (ref "J2") (pin "5") (pinfunction "SHIELD1_5") (pintype "passive"))
      (node (ref "J2") (pin "6") (pinfunction "SHIELD2_6") (pintype "passive"))
      (node (ref "J4") (pin "A1") (pinfunction "GND1_A1") (pintype "passive"))
      (node (ref "J4") (pin "A12") (pinfunction "GND2_A12") (pintype "passive"))
      (node (ref "J4") (pin "B1") (pinfunction "GND3_B1") (pintype "passive"))
      (node (ref "J4") (pin "B12") (pinfunction "GND4_B12") (pintype "passive"))
      (node (ref "J4") (pin "C1") (pinfunction "SHIELD1_C1") (pintype "passive"))
      (node (ref "J4") (pin "C2") (pinfunction "SHIELD2_C2") (pintype "passive"))
      (node (ref "J4") (pin "C3") (pinfunction "SHIELD3_C3") (pintype "passive"))
      (node (ref "J4") (pin "C4") (pinfunction "SHIELD4_C4") (pintype "passive"))
      (node (ref "Q1") (pin "3") (pinfunction "S2_3") (pintype "passive"))
      (node (ref "Q2") (pin "3") (pinfunction "S2_3") (pintype "passive"))
      (node (ref "Q3") (pin "3") (pinfunction "S2_3") (pintype "passive"))
      (node (ref "Q4") (pin "3") (pinfunction "S2_3") (pintype "passive"))
      (node (ref "Q7") (pin "2") (pinfunction "E_2") (pintype "passive"))
      (node (ref "Q9") (pin "1") (pinfunction "S1_1") (pintype "passive"))
      (node (ref "R12") (pin "1") (pinfunction "1_1") (pintype "passive"))
      (node (ref "R2") (pin "1") (pinfunction "1_1") (pintype "passive"))
      (node (ref "R28") (pin "1") (pinfunction "1_1") (pintype "passive"))
      (node (ref "R31") (pin "2") (pinfunction "2_2") (pintype "passive"))
      (node (ref "R33") (pin "2") (pinfunction "2_2") (pintype "passive"))
      (node (ref "R6") (pin "2") (pinfunction "2_2") (pintype "passive"))
      (node (ref "R7") (pin "1") (pinfunction "1_1") (pintype "passive"))
      (node (ref "S1") (pin "2") (pinfunction "2_2") (pintype "passive"))
      (node (ref "U3") (pin "13") (pinfunction "AGND_13") (pintype "passive"))
      (node (ref "U3") (pin "24") (pinfunction "LED4/I2C_24") (pintype "passive"))
      (node (ref "U3") (pin "41") (pinfunction "EPAD_41") (pintype "passive"))
      (node (ref "U4") (pin "1") (pinfunction "VSS_1") (pintype "passive"))
      (node (ref "ZD3") (pin "1") (pinfunction "A_1") (pintype "passive"))
    )
    (net (code "43") (name "Net-(C17-Pad2)") (class "Default")
      (node (ref "C17") (pin "2") (pinfunction "2_2") (pintype "passive"))
      (node (ref "R10") (pin "2") (pinfunction "2_2") (pintype "passive"))
    )
    (net (code "44") (name "Net-(D1-A)") (class "Default")
      (node (ref "D1") (pin "1") (pinfunction "A_1") (pintype "passive"))
      (node (ref "R13") (pin "1") (pinfunction "1_1") (pintype "passive"))
    )
    (net (code "45") (name "Net-(D2-K)") (class "Default")
      (node (ref "D2") (pin "2") (pinfunction "K_2") (pintype "passive"))
      (node (ref "R14") (pin "1") (pinfunction "1_1") (pintype "passive"))
    )
    (net (code "46") (name "Net-(D3-Pad3)") (class "Default")
      (node (ref "D3") (pin "3") (pintype "passive"))
      (node (ref "R15") (pin "2") (pinfunction "2_2") (pintype "passive"))
    )
    (net (code "47") (name "Net-(J5-DM)") (class "Default")
      (node (ref "J5") (pin "2") (pinfunction "DM_2") (pintype "passive"))
      (node (ref "J5") (pin "3") (pinfunction "DP_3") (pintype "passive"))
    )
    (net (code "48") (name "Net-(J5-GND)") (class "Default")
      (node (ref "J5") (pin "4") (pinfunction "GND_4") (pintype "passive"))
      (node (ref "R16") (pin "2") (pinfunction "2_2") (pintype "passive"))
      (node (ref "R28") (pin "2") (pinfunction "2_2") (pintype "passive"))
    )
    (net (code "49") (name "Net-(J5-VBUS)") (class "Default")
      (node (ref "C22") (pin "2") (pinfunction "2_2") (pintype "passive"))
      (node (ref "J5") (pin "1") (pinfunction "VBUS_1") (pintype "passive"))
      (node (ref "Q10") (pin "3") (pinfunction "D_3") (pintype "passive"))
      (node (ref "R17") (pin "1") (pinfunction "1_1") (pintype "passive"))
      (node (ref "R18") (pin "2") (pinfunction "2_2") (pintype "passive"))
    )
    (net (code "50") (name "Net-(J6-Pad1)") (class "Default")
      (node (ref "J6") (pin "1") (pinfunction "1_1") (pintype "passive"))
      (node (ref "R23") (pin "1") (pinfunction "1_1") (pintype "passive"))
    )
    (net (code "51") (name "Net-(J6-Pad2)") (class "Default")
      (node (ref "J6") (pin "2") (pinfunction "2_2") (pintype "passive"))
      (node (ref "R24") (pin "1") (pinfunction "1_1") (pintype "passive"))
    )
    (net (code "52") (name "Net-(J6-Pad3)") (class "Default")
      (node (ref "J6") (pin "3") (pinfunction "3_3") (pintype "passive"))
      (node (ref "R25") (pin "1") (pinfunction "1_1") (pintype "passive"))
    )
    (net (code "53") (name "Net-(J6-Pad4)") (class "Default")
      (node (ref "J6") (pin "4") (pinfunction "4_4") (pintype "passive"))
      (node (ref "R26") (pin "1") (pinfunction "1_1") (pintype "passive"))
    )
    (net (code "54") (name "Net-(J6-Pad5)") (class "Default")
      (node (ref "J6") (pin "5") (pinfunction "5_5") (pintype "passive"))
      (node (ref "R29") (pin "1") (pinfunction "1_1") (pintype "passive"))
    )
    (net (code "55") (name "Net-(J6-Pad6)") (class "Default")
      (node (ref "J6") (pin "6") (pinfunction "6_6") (pintype "passive"))
      (node (ref "R30") (pin "1") (pinfunction "1_1") (pintype "passive"))
    )
    (net (code "56") (name "Net-(Q1-D1)") (class "Default")
      (node (ref "Q1") (pin "2") (pinfunction "D1_2") (pintype "passive"))
      (node (ref "Q2") (pin "5") (pinfunction "D2_5") (pintype "passive"))
    )
    (net (code "57") (name "Net-(Q1-G1)") (class "Default")
      (node (ref "Q1") (pin "6") (pinfunction "G1_6") (pintype "passive"))
      (node (ref "Q2") (pin "6") (pinfunction "G1_6") (pintype "passive"))
      (node (ref "Q3") (pin "6") (pinfunction "G1_6") (pintype "passive"))
      (node (ref "Q4") (pin "6") (pinfunction "G1_6") (pintype "passive"))
      (node (ref "U1") (pin "1") (pinfunction "OD_1") (pintype "passive"))
    )
    (net (code "58") (name "Net-(Q1-G2)") (class "Default")
      (node (ref "Q1") (pin "4") (pinfunction "G2_4") (pintype "passive"))
      (node (ref "Q2") (pin "4") (pinfunction "G2_4") (pintype "passive"))
      (node (ref "Q3") (pin "4") (pinfunction "G2_4") (pintype "passive"))
      (node (ref "Q4") (pin "4") (pinfunction "G2_4") (pintype "passive"))
      (node (ref "U1") (pin "3") (pinfunction "OC_3") (pintype "passive"))
    )
    (net (code "59") (name "Net-(Q2-D1)") (class "Default")
      (node (ref "Q2") (pin "2") (pinfunction "D1_2") (pintype "passive"))
      (node (ref "Q3") (pin "5") (pinfunction "D2_5") (pintype "passive"))
    )
    (net (code "60") (name "Net-(Q3-D1)") (class "Default")
      (node (ref "Q3") (pin "2") (pinfunction "D1_2") (pintype "passive"))
      (node (ref "Q4") (pin "5") (pinfunction "D2_5") (pintype "passive"))
    )
    (net (code "61") (name "Net-(Q7-B)") (class "Default")
      (node (ref "Q7") (pin "1") (pinfunction "B_1") (pintype "passive"))
      (node (ref "R4") (pin "2") (pinfunction "2_2") (pintype "passive"))
      (node (ref "R6") (pin "1") (pinfunction "1_1") (pintype "passive"))
    )
    (net (code "62") (name "Net-(Q7-C)") (class "Default")
      (node (ref "Q7") (pin "3") (pinfunction "C_3") (pintype "passive"))
      (node (ref "Q9") (pin "6") (pinfunction "G1_6") (pintype "passive"))
      (node (ref "R3") (pin "2") (pinfunction "2_2") (pintype "passive"))
    )
    (net (code "63") (name "Net-(Q9-D1)") (class "Default")
      (node (ref "Q9") (pin "2") (pinfunction "D1_2") (pintype "passive"))
      (node (ref "Q9") (pin "5") (pinfunction "D2_5") (pintype "passive"))
    )
    (net (code "64") (name "Net-(Q9-G2)") (class "Default")
      (node (ref "C18") (pin "1") (pinfunction "1_1") (pintype "passive"))
      (node (ref "Q9") (pin "4") (pinfunction "G2_4") (pintype "passive"))
      (node (ref "U2") (pin "1") (pinfunction "GATE_1") (pintype "passive"))
    )
    (net (code "65") (name "Net-(Q9-S2)") (class "Default")
      (node (ref "C16") (pin "1") (pinfunction "1_1") (pintype "passive"))
      (node (ref "C17") (pin "1") (pinfunction "1_1") (pintype "passive"))
      (node (ref "C18") (pin "2") (pinfunction "2_2") (pintype "passive"))
      (node (ref "J3") (pin "1") (pinfunction "1_1") (pintype "passive"))
      (node (ref "J3") (pin "10") (pinfunction "10_10") (pintype "passive"))
      (node (ref "J3") (pin "2") (pinfunction "2_2") (pintype "passive"))
      (node (ref "Q9") (pin "3") (pinfunction "S2_3") (pintype "passive"))
      (node (ref "R11") (pin "2") (pinfunction "2_2") (pintype "passive"))
      (node (ref "U2") (pin "2") (pinfunction "GND_2") (pintype "passive"))
      (node (ref "ZD2") (pin "1") (pinfunction "A_1") (pintype "passive"))
    )
    (net (code "66") (name "Net-(Q10-G)") (class "Default")
      (node (ref "Q10") (pin "1") (pinfunction "G_1") (pintype "passive"))
      (node (ref "Q11") (pin "3") (pinfunction "D_3") (pintype "passive"))
      (node (ref "Q12") (pin "1") (pinfunction "G_1") (pintype "passive"))
      (node (ref "R31") (pin "1") (pinfunction "1_1") (pintype "passive"))
    )
    (net (code "67") (name "Net-(Q11-G)") (class "Default")
      (node (ref "Q11") (pin "1") (pinfunction "G_1") (pintype "passive"))
      (node (ref "R27") (pin "2") (pinfunction "2_2") (pintype "passive"))
      (node (ref "R33") (pin "1") (pinfunction "1_1") (pintype "passive"))
    )
    (net (code "68") (name "Net-(Q12-S)") (class "Default")
      (node (ref "Q12") (pin "2") (pinfunction "S_2") (pintype "passive"))
      (node (ref "R17") (pin "2") (pinfunction "2_2") (pintype "passive"))
    )
    (net (code "69") (name "Net-(U1-CS)") (class "Default")
      (node (ref "R2") (pin "2") (pinfunction "2_2") (pintype "passive"))
      (node (ref "U1") (pin "2") (pinfunction "CS_2") (pintype "passive"))
    )
    (net (code "70") (name "Net-(U1-VCC)") (class "Default")
      (node (ref "C1") (pin "2") (pinfunction "2_2") (pintype "passive"))
      (node (ref "R1") (pin "1") (pinfunction "1_1") (pintype "passive"))
      (node (ref "U1") (pin "5") (pinfunction "VCC_5") (pintype "passive"))
    )
    (net (code "71") (name "Net-(U2-VDD)") (class "Default")
      (node (ref "C16") (pin "2") (pinfunction "2_2") (pintype "passive"))
      (node (ref "R11") (pin "1") (pinfunction "1_1") (pintype "passive"))
      (node (ref "R8") (pin "1") (pinfunction "1_1") (pintype "passive"))
      (node (ref "R9") (pin "2") (pinfunction "2_2") (pintype "passive"))
      (node (ref "U2") (pin "5") (pinfunction "VDD_5") (pintype "passive"))
      (node (ref "ZD2") (pin "2") (pinfunction "K_2") (pintype "passive"))
    )
    (net (code "72") (name "Net-(ZD1-A)") (class "Default")
      (node (ref "R4") (pin "1") (pinfunction "1_1") (pintype "passive"))
      (node (ref "ZD1") (pin "1") (pinfunction "A_1") (pintype "passive"))
    )
    (net (code "73") (name "VBUS_B") (class "Default")
      (node (ref "C4") (pin "2") (pinfunction "2_2") (pintype "passive"))
      (node (ref "J1") (pin "1") (pinfunction "VBUS_1") (pintype "passive"))
      (node (ref "J3") (pin "6") (pinfunction "6_6") (pintype "passive"))
      (node (ref "Q5") (pin "1") (pinfunction "S1_1") (pintype "passive"))
      (node (ref "Q5") (pin "3") (pinfunction "S2_3") (pintype "passive"))
      (node (ref "R10") (pin "1") (pinfunction "1_1") (pintype "passive"))
      (node (ref "R3") (pin "1") (pinfunction "1_1") (pintype "passive"))
      (node (ref "R9") (pin "1") (pinfunction "1_1") (pintype "passive"))
      (node (ref "U3") (pin "30") (pinfunction "VBUS_B_30") (pintype "passive"))
      (node (ref "ZD1") (pin "2") (pinfunction "K_2") (pintype "passive"))
    )
    (net (code "74") (name "unconnected-(J3-Pad3)") (class "Default")
      (node (ref "J3") (pin "3") (pinfunction "3_3") (pintype "passive"))
    )
    (net (code "75") (name "unconnected-(J3-Pad4)") (class "Default")
      (node (ref "J3") (pin "4") (pinfunction "4_4") (pintype "passive"))
    )
    (net (code "76") (name "unconnected-(J3-Pad7)") (class "Default")
      (node (ref "J3") (pin "7") (pinfunction "7_7") (pintype "passive"))
    )
    (net (code "77") (name "unconnected-(J3-Pad8)") (class "Default")
      (node (ref "J3") (pin "8") (pinfunction "8_8") (pintype "passive"))
    )
    (net (code "78") (name "unconnected-(J4-SBU1-PadA8)") (class "Default")
      (node (ref "J4") (pin "A8") (pinfunction "SBU1_A8") (pintype "passive"))
    )
    (net (code "79") (name "unconnected-(J4-SBU2-PadB8)") (class "Default")
      (node (ref "J4") (pin "B8") (pinfunction "SBU2_B8") (pintype "passive"))
    )
    (net (code "80") (name "unconnected-(J4-SSRXn1-PadB10)") (class "Default")
      (node (ref "J4") (pin "B10") (pinfunction "SSRXn1_B10") (pintype "passive"))
    )
    (net (code "81") (name "unconnected-(J4-SSRXn2-PadA10)") (class "Default")
      (node (ref "J4") (pin "A10") (pinfunction "SSRXn2_A10") (pintype "passive"))
    )
    (net (code "82") (name "unconnected-(J4-SSRXp1-PadB11)") (class "Default")
      (node (ref "J4") (pin "B11") (pinfunction "SSRXp1_B11") (pintype "passive"))
    )
    (net (code "83") (name "unconnected-(J4-SSRXp2-PadA11)") (class "Default")
      (node (ref "J4") (pin "A11") (pinfunction "SSRXp2_A11") (pintype "passive"))
    )
    (net (code "84") (name "unconnected-(J4-SSTXn1-PadA3)") (class "Default")
      (node (ref "J4") (pin "A3") (pinfunction "SSTXn1_A3") (pintype "passive"))
    )
    (net (code "85") (name "unconnected-(J4-SSTXn2-PadB3)") (class "Default")
      (node (ref "J4") (pin "B3") (pinfunction "SSTXn2_B3") (pintype "passive"))
    )
    (net (code "86") (name "unconnected-(J4-SSTXp1-PadA2)") (class "Default")
      (node (ref "J4") (pin "A2") (pinfunction "SSTXp1_A2") (pintype "passive"))
    )
    (net (code "87") (name "unconnected-(J4-SSTXp2-PadB2)") (class "Default")
      (node (ref "J4") (pin "B2") (pinfunction "SSTXp2_B2") (pintype "passive"))
    )
    (net (code "88") (name "unconnected-(J5-SHIELD1-Pad5)") (class "Default")
      (node (ref "J5") (pin "5") (pinfunction "SHIELD1_5") (pintype "passive"))
    )
    (net (code "89") (name "unconnected-(J5-SHIELD2-Pad6)") (class "Default")
      (node (ref "J5") (pin "6") (pinfunction "SHIELD2_6") (pintype "passive"))
    )
    (net (code "90") (name "unconnected-(Q1-D2-Pad5)") (class "Default")
      (node (ref "Q1") (pin "5") (pinfunction "D2_5") (pintype "passive"))
    )
    (net (code "91") (name "unconnected-(Q4-D1-Pad2)") (class "Default")
      (node (ref "Q4") (pin "2") (pinfunction "D1_2") (pintype "passive"))
    )
    (net (code "92") (name "unconnected-(Q5-D1-Pad2)") (class "Default")
      (node (ref "Q5") (pin "2") (pinfunction "D1_2") (pintype "passive"))
    )
    (net (code "93") (name "unconnected-(Q6-D1-Pad2)") (class "Default")
      (node (ref "Q6") (pin "2") (pinfunction "D1_2") (pintype "passive"))
    )
    (net (code "94") (name "unconnected-(Q8-D1-Pad2)") (class "Default")
      (node (ref "Q8") (pin "2") (pinfunction "D1_2") (pintype "passive"))
    )
    (net (code "95") (name "unconnected-(U1-TD-Pad4)") (class "Default")
      (node (ref "U1") (pin "4") (pinfunction "TD_4") (pintype "passive"))
    )
    (net (code "96") (name "unconnected-(U2-NC1-Pad3)") (class "Default")
      (node (ref "U2") (pin "3") (pinfunction "NC1_3") (pintype "passive"))
    )
    (net (code "97") (name "unconnected-(U2-NC2-Pad4)") (class "Default")
      (node (ref "U2") (pin "4") (pinfunction "NC2_4") (pintype "passive"))
    )
    (net (code "98") (name "unconnected-(U4-PA2-Pad4)") (class "Default")
      (node (ref "U4") (pin "4") (pinfunction "PA2_4") (pintype "passive"))
    )
    (net (code "99") (name "unconnected-(U4-PB3-Pad9)") (class "Default")
      (node (ref "U4") (pin "9") (pinfunction "PB3_9") (pintype "passive"))
    )
  )
)
